# BatteryPack.net
KiCad netlist of a schematic drawn in Altium Designer
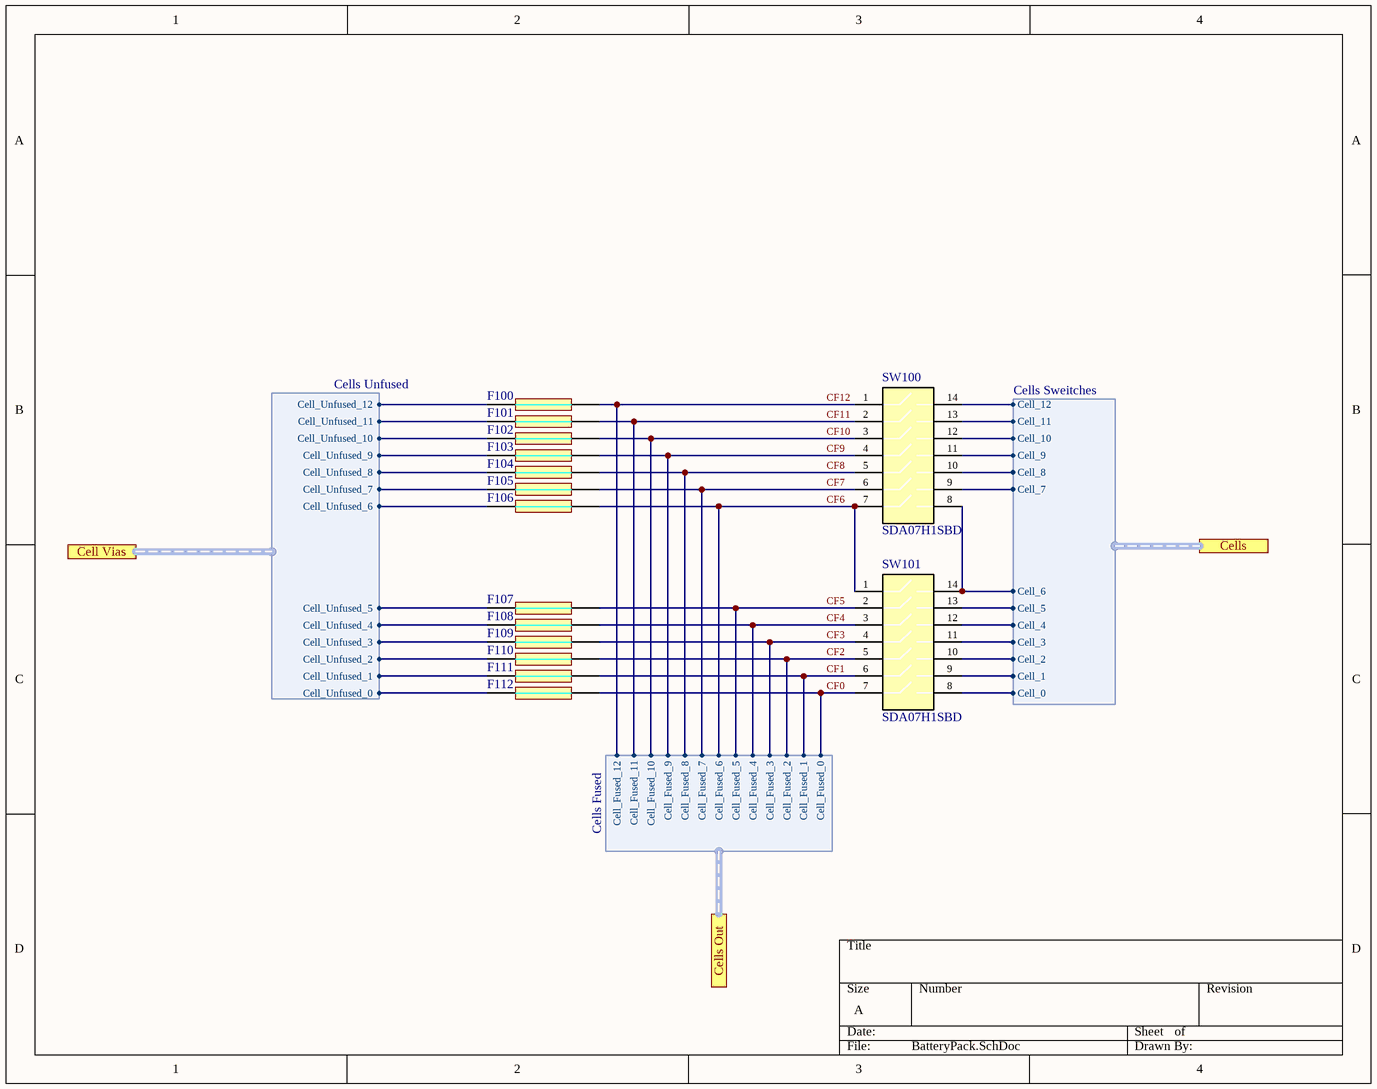
[diagram p0: BatteryPack.SchDoc]

(export (version "E")
  (design (tool "Eeschema 10.0.6"))
  (components
    (comp (ref "F100")
      (value "SFP200F")
      (footprint "DIOC3216X12N")
      (description "Surface Mount Fuses VERY FAST GLASS CER 63V 2A SZ 1206")
      (libsource (lib "SFP200F") (part "SFP200F"))
    )
    (comp (ref "F101")
      (value "SFP200F")
      (footprint "DIOC3216X12N")
      (description "Surface Mount Fuses VERY FAST GLASS CER 63V 2A SZ 1206")
      (libsource (lib "SFP200F") (part "SFP200F"))
    )
    (comp (ref "F102")
      (value "SFP200F")
      (footprint "DIOC3216X12N")
      (description "Surface Mount Fuses VERY FAST GLASS CER 63V 2A SZ 1206")
      (libsource (lib "SFP200F") (part "SFP200F"))
    )
    (comp (ref "F103")
      (value "SFP200F")
      (footprint "DIOC3216X12N")
      (description "Surface Mount Fuses VERY FAST GLASS CER 63V 2A SZ 1206")
      (libsource (lib "SFP200F") (part "SFP200F"))
    )
    (comp (ref "F104")
      (value "SFP200F")
      (footprint "DIOC3216X12N")
      (description "Surface Mount Fuses VERY FAST GLASS CER 63V 2A SZ 1206")
      (libsource (lib "SFP200F") (part "SFP200F"))
    )
    (comp (ref "F105")
      (value "SFP200F")
      (footprint "DIOC3216X12N")
      (description "Surface Mount Fuses VERY FAST GLASS CER 63V 2A SZ 1206")
      (libsource (lib "SFP200F") (part "SFP200F"))
    )
    (comp (ref "F106")
      (value "SFP200F")
      (footprint "DIOC3216X12N")
      (description "Surface Mount Fuses VERY FAST GLASS CER 63V 2A SZ 1206")
      (libsource (lib "SFP200F") (part "SFP200F"))
    )
    (comp (ref "F107")
      (value "SFP200F")
      (footprint "DIOC3216X12N")
      (description "Surface Mount Fuses VERY FAST GLASS CER 63V 2A SZ 1206")
      (libsource (lib "SFP200F") (part "SFP200F"))
    )
    (comp (ref "F108")
      (value "SFP200F")
      (footprint "DIOC3216X12N")
      (description "Surface Mount Fuses VERY FAST GLASS CER 63V 2A SZ 1206")
      (libsource (lib "SFP200F") (part "SFP200F"))
    )
    (comp (ref "F109")
      (value "SFP200F")
      (footprint "DIOC3216X12N")
      (description "Surface Mount Fuses VERY FAST GLASS CER 63V 2A SZ 1206")
      (libsource (lib "SFP200F") (part "SFP200F"))
    )
    (comp (ref "F110")
      (value "SFP200F")
      (footprint "DIOC3216X12N")
      (description "Surface Mount Fuses VERY FAST GLASS CER 63V 2A SZ 1206")
      (libsource (lib "SFP200F") (part "SFP200F"))
    )
    (comp (ref "F111")
      (value "SFP200F")
      (footprint "DIOC3216X12N")
      (description "Surface Mount Fuses VERY FAST GLASS CER 63V 2A SZ 1206")
      (libsource (lib "SFP200F") (part "SFP200F"))
    )
    (comp (ref "F112")
      (value "SFP200F")
      (footprint "DIOC3216X12N")
      (description "Surface Mount Fuses VERY FAST GLASS CER 63V 2A SZ 1206")
      (libsource (lib "SFP200F") (part "SFP200F"))
    )
    (comp (ref "SW100")
      (value "SDA07H1SBD")
      (footprint "7 pos Dip-Switch")
      (description "Dip Switch SPST 7 Position Surface Mount Slide (Standard) Actuator 25mA 24VDC")
      (libsource (lib "SDA07H1SBD") (part "Dip Switches"))
    )
    (comp (ref "SW101")
      (value "SDA07H1SBD")
      (footprint "7 pos Dip-Switch")
      (description "Dip Switch SPST 7 Position Surface Mount Slide (Standard) Actuator 25mA 24VDC")
      (libsource (lib "SDA07H1SBD") (part "Dip Switches"))
    )
  )
  (nets
    (net (code "5") (name "/CF0") (class "Default")
      (node (ref "F112") (pin "2") (pinfunction "2_2") (pintype "passive"))
      (node (ref "SW101") (pin "7") (pinfunction "7_7") (pintype "passive"))
    )
    (net (code "6") (name "/CF1") (class "Default")
      (node (ref "F111") (pin "2") (pinfunction "2_2") (pintype "passive"))
      (node (ref "SW101") (pin "6") (pinfunction "6_6") (pintype "passive"))
    )
    (net (code "7") (name "/CF2") (class "Default")
      (node (ref "F110") (pin "2") (pinfunction "2_2") (pintype "passive"))
      (node (ref "SW101") (pin "5") (pinfunction "5_5") (pintype "passive"))
    )
    (net (code "8") (name "/CF3") (class "Default")
      (node (ref "F109") (pin "2") (pinfunction "2_2") (pintype "passive"))
      (node (ref "SW101") (pin "4") (pinfunction "4_4") (pintype "passive"))
    )
    (net (code "9") (name "/CF4") (class "Default")
      (node (ref "F108") (pin "2") (pinfunction "2_2") (pintype "passive"))
      (node (ref "SW101") (pin "3") (pinfunction "3_3") (pintype "passive"))
    )
    (net (code "10") (name "/CF5") (class "Default")
      (node (ref "F107") (pin "2") (pinfunction "2_2") (pintype "passive"))
      (node (ref "SW101") (pin "2") (pinfunction "2_2") (pintype "passive"))
    )
    (net (code "11") (name "/CF6") (class "Default")
      (node (ref "F106") (pin "2") (pinfunction "2_2") (pintype "passive"))
      (node (ref "SW100") (pin "7") (pinfunction "7_7") (pintype "passive"))
      (node (ref "SW101") (pin "1") (pinfunction "1_1") (pintype "passive"))
    )
    (net (code "12") (name "/CF7") (class "Default")
      (node (ref "F105") (pin "2") (pinfunction "2_2") (pintype "passive"))
      (node (ref "SW100") (pin "6") (pinfunction "6_6") (pintype "passive"))
    )
    (net (code "13") (name "/CF8") (class "Default")
      (node (ref "F104") (pin "2") (pinfunction "2_2") (pintype "passive"))
      (node (ref "SW100") (pin "5") (pinfunction "5_5") (pintype "passive"))
    )
    (net (code "14") (name "/CF9") (class "Default")
      (node (ref "F103") (pin "2") (pinfunction "2_2") (pintype "passive"))
      (node (ref "SW100") (pin "4") (pinfunction "4_4") (pintype "passive"))
    )
    (net (code "15") (name "/CF10") (class "Default")
      (node (ref "F102") (pin "2") (pinfunction "2_2") (pintype "passive"))
      (node (ref "SW100") (pin "3") (pinfunction "3_3") (pintype "passive"))
    )
    (net (code "16") (name "/CF11") (class "Default")
      (node (ref "F101") (pin "2") (pinfunction "2_2") (pintype "passive"))
      (node (ref "SW100") (pin "2") (pinfunction "2_2") (pintype "passive"))
    )
    (net (code "17") (name "/CF12") (class "Default")
      (node (ref "F100") (pin "2") (pinfunction "2_2") (pintype "passive"))
      (node (ref "SW100") (pin "1") (pinfunction "1_1") (pintype "passive"))
    )
    (net (code "18") (name "/Cell_0") (class "Default")
      (node (ref "SW101") (pin "8") (pinfunction "8_8") (pintype "passive"))
    )
    (net (code "19") (name "/Cell_1") (class "Default")
      (node (ref "SW101") (pin "9") (pinfunction "9_9") (pintype "passive"))
    )
    (net (code "20") (name "/Cell_2") (class "Default")
      (node (ref "SW101") (pin "10") (pinfunction "10_10") (pintype "passive"))
    )
    (net (code "21") (name "/Cell_3") (class "Default")
      (node (ref "SW101") (pin "11") (pinfunction "11_11") (pintype "passive"))
    )
    (net (code "22") (name "/Cell_4") (class "Default")
      (node (ref "SW101") (pin "12") (pinfunction "12_12") (pintype "passive"))
    )
    (net (code "23") (name "/Cell_5") (class "Default")
      (node (ref "SW101") (pin "13") (pinfunction "13_13") (pintype "passive"))
    )
    (net (code "24") (name "/Cell_6") (class "Default")
      (node (ref "SW100") (pin "8") (pinfunction "8_8") (pintype "passive"))
      (node (ref "SW101") (pin "14") (pinfunction "14_14") (pintype "passive"))
    )
    (net (code "25") (name "/Cell_7") (class "Default")
      (node (ref "SW100") (pin "9") (pinfunction "9_9") (pintype "passive"))
    )
    (net (code "26") (name "/Cell_8") (class "Default")
      (node (ref "SW100") (pin "10") (pinfunction "10_10") (pintype "passive"))
    )
    (net (code "27") (name "/Cell_9") (class "Default")
      (node (ref "SW100") (pin "11") (pinfunction "11_11") (pintype "passive"))
    )
    (net (code "28") (name "/Cell_10") (class "Default")
      (node (ref "SW100") (pin "12") (pinfunction "12_12") (pintype "passive"))
    )
    (net (code "29") (name "/Cell_11") (class "Default")
      (node (ref "SW100") (pin "13") (pinfunction "13_13") (pintype "passive"))
    )
    (net (code "30") (name "/Cell_12") (class "Default")
      (node (ref "SW100") (pin "14") (pinfunction "14_14") (pintype "passive"))
    )
    (net (code "31") (name "/Cell_Unfused_0") (class "Default")
      (node (ref "F112") (pin "1") (pinfunction "1_1") (pintype "passive"))
    )
    (net (code "32") (name "/Cell_Unfused_1") (class "Default")
      (node (ref "F111") (pin "1") (pinfunction "1_1") (pintype "passive"))
    )
    (net (code "33") (name "/Cell_Unfused_2") (class "Default")
      (node (ref "F110") (pin "1") (pinfunction "1_1") (pintype "passive"))
    )
    (net (code "34") (name "/Cell_Unfused_3") (class "Default")
      (node (ref "F109") (pin "1") (pinfunction "1_1") (pintype "passive"))
    )
    (net (code "35") (name "/Cell_Unfused_4") (class "Default")
      (node (ref "F108") (pin "1") (pinfunction "1_1") (pintype "passive"))
    )
    (net (code "36") (name "/Cell_Unfused_5") (class "Default")
      (node (ref "F107") (pin "1") (pinfunction "1_1") (pintype "passive"))
    )
    (net (code "37") (name "/Cell_Unfused_6") (class "Default")
      (node (ref "F106") (pin "1") (pinfunction "1_1") (pintype "passive"))
    )
    (net (code "38") (name "/Cell_Unfused_7") (class "Default")
      (node (ref "F105") (pin "1") (pinfunction "1_1") (pintype "passive"))
    )
    (net (code "39") (name "/Cell_Unfused_8") (class "Default")
      (node (ref "F104") (pin "1") (pinfunction "1_1") (pintype "passive"))
    )
    (net (code "40") (name "/Cell_Unfused_9") (class "Default")
      (node (ref "F103") (pin "1") (pinfunction "1_1") (pintype "passive"))
    )
    (net (code "41") (name "/Cell_Unfused_10") (class "Default")
      (node (ref "F102") (pin "1") (pinfunction "1_1") (pintype "passive"))
    )
    (net (code "42") (name "/Cell_Unfused_11") (class "Default")
      (node (ref "F101") (pin "1") (pinfunction "1_1") (pintype "passive"))
    )
    (net (code "43") (name "/Cell_Unfused_12") (class "Default")
      (node (ref "F100") (pin "1") (pinfunction "1_1") (pintype "passive"))
    )
  )
)
